# 1_8V_POWER.net
KiCad netlist of a schematic drawn in Altium Designer
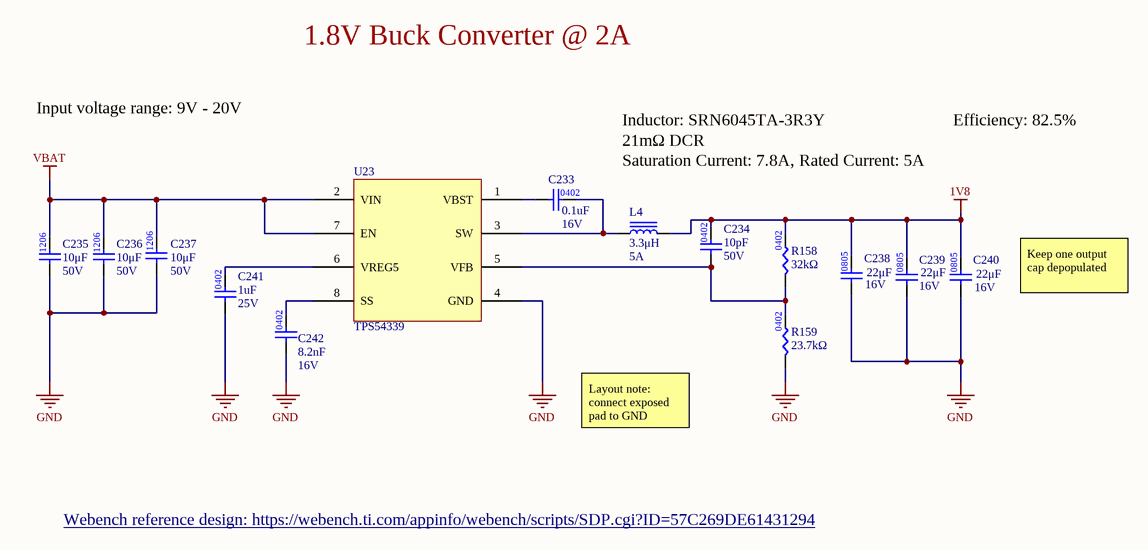
[diagram p0: 1.8V POWER.SchDoc]

(export (version "E")
  (design (tool "Eeschema 10.0.6"))
  (components
    (comp (ref "C233")
      (value "CAP_0.1uF_16V_X7R_0402")
      (footprint "CAP0402")
      (description "Ceramic Capacitor, Ceramic")
      (fields
        (field (name "MANUFACTURER") "Taiyo Yuden")
        (field (name "MANUFACTURER PART NUMBER") "LMK212AC6106MD-T")
        (field (name "RATED DC VOLTAGE (URDC)") "16V")
        (field (name "CAPACITANCE") "0.1uF")
      )
      (libsource (lib "UWRT_Schematic_Library_2020") (part "CAP_0.1uF_16V_X7R_0402"))
    )
    (comp (ref "C234")
      (value "CAP_10pF_50V_0402")
      (footprint "CAP0402")
      (fields (field (name "CAPACITANCE") "10pF") (field (name "VOLTAGE") "50V"))
      (libsource (lib "UWRT_Schematic_Library_2020") (part "CAP_10pF_50V_0402"))
    )
    (comp (ref "C235")
      (value "10μF")
      (footprint "CAP1210")
      (description "CAP CER 10UF 50V X7R 1210")
      (fields (field (name "VOLTAGE RATING") "50V") (field (name "Comment") "CAP_10uF_50V_1210"))
      (libsource (lib "UWRT_Schematic_Library_2020") (part "CAP_10uF_50V_1210"))
    )
    (comp (ref "C236")
      (value "10μF")
      (footprint "CAP1210")
      (description "CAP CER 10UF 50V X7R 1210")
      (fields (field (name "VOLTAGE RATING") "50V") (field (name "Comment") "CAP_10uF_50V_1210"))
      (libsource (lib "UWRT_Schematic_Library_2020") (part "CAP_10uF_50V_1210"))
    )
    (comp (ref "C237")
      (value "10μF")
      (footprint "CAP1210")
      (description "CAP CER 10UF 50V X7R 1210")
      (fields (field (name "VOLTAGE RATING") "50V") (field (name "Comment") "CAP_10uF_50V_1210"))
      (libsource (lib "UWRT_Schematic_Library_2020") (part "CAP_10uF_50V_1210"))
    )
    (comp (ref "C238")
      (value "22μF")
      (footprint "CAP2012")
      (description "CAP CER 22UF 16V X5R 0805")
      (fields (field (name "VOLTAGE RATING") "16V") (field (name "Comment") "CAP_22uF_16V_0805"))
      (libsource (lib "UWRT_Schematic_Library_2020") (part "CAP_22uF_16V_0805"))
    )
    (comp (ref "C239")
      (value "22μF")
      (footprint "CAP2012")
      (description "CAP CER 22UF 16V X5R 0805")
      (fields (field (name "VOLTAGE RATING") "16V") (field (name "Comment") "CAP_22uF_16V_0805"))
      (libsource (lib "UWRT_Schematic_Library_2020") (part "CAP_22uF_16V_0805"))
    )
    (comp (ref "C240")
      (value "22μF")
      (footprint "CAP2012")
      (description "CAP CER 22UF 16V X5R 0805")
      (fields (field (name "VOLTAGE RATING") "16V") (field (name "Comment") "CAP_22uF_16V_0805"))
      (libsource (lib "UWRT_Schematic_Library_2020") (part "CAP_22uF_16V_0805"))
    )
    (comp (ref "C241")
      (value "CAP_1uF_25V_0402")
      (footprint "CAP0402")
      (description "±10% 25V Ceramic Capacitor X5R 0402 (1005 Metric)")
      (fields (field (name "CAPACITANCE") "1uF") (field (name "VOLTAGE") "25V"))
      (libsource (lib "UWRT_Schematic_Library_2020") (part "CAP_1uF_25V_0402"))
    )
    (comp (ref "C242")
      (value "CAP_8.2nF_16V_0402")
      (footprint "CAP0402")
      (description "8200 pF ±10% 16V Ceramic Capacitor X7R 0402 (1005 Metric)")
      (fields (field (name "CAPACITANCE") "8.2nF") (field (name "VOLTAGE") "16V"))
      (libsource (lib "UWRT_Schematic_Library_2020") (part "CAP_8.2nF_16V_0402"))
    )
    (comp (ref "L4")
      (value "IND_3.3uH_5A")
      (footprint "IND_SRN6045TA-3R3Y")
      (description "FIXED IND 3.3UH 5A 21 MOHM SMD")
      (fields (field (name "CURRENT RATING") "5A") (field (name "INDUCTANCE") "3.3μH"))
      (libsource (lib "UWRT_Schematic_Library_2020") (part "IND_3.3uH_5A"))
    )
    (comp (ref "R158")
      (value "32kΩ")
      (footprint "RES0402")
      (description "RES 32K OHM 1% 1/16W 0402")
      (fields (field (name "TOLERANCE") "1%") (field (name "Comment") "RES_32kΩ_0402_1%"))
      (libsource (lib "UWRT_Schematic_Library_2020") (part "RES_32kΩ_0402_1%"))
    )
    (comp (ref "R159")
      (value "23.7kΩ")
      (footprint "RES0402")
      (description "RES 23.7K OHM 1% 1/16W 0402")
      (fields (field (name "POWER") "0.063W, 1/16W") (field (name "TOLERANCE") "1%"))
      (libsource (lib "UWRT_Schematic_Library_2020") (part "RES_23.7kΩ_0402_1%"))
    )
    (comp (ref "U23")
      (value "TPS54339")
      (footprint "VREG_LM5017MR/NOPB")
      (description "IC REG BUCK ADJUSTABLE 3A 8SOPWR")
      (libsource (lib "UWRT_Schematic_Library_2020") (part "TPS54339"))
    )
  )
  (nets
    (net (code "1") (name "1V8") (class "Default")
      (node (ref "C234") (pin "2") (pinfunction "2_2") (pintype "passive"))
      (node (ref "C238") (pin "2") (pinfunction "2_2") (pintype "passive"))
      (node (ref "C239") (pin "2") (pinfunction "2_2") (pintype "passive"))
      (node (ref "C240") (pin "2") (pinfunction "2_2") (pintype "passive"))
      (node (ref "L4") (pin "2") (pinfunction "2_2") (pintype "passive"))
      (node (ref "R158") (pin "2") (pinfunction "2_2") (pintype "passive"))
    )
    (net (code "2") (name "GND") (class "Default")
      (node (ref "C235") (pin "1") (pinfunction "1_1") (pintype "passive"))
      (node (ref "C236") (pin "1") (pinfunction "1_1") (pintype "passive"))
      (node (ref "C237") (pin "1") (pinfunction "1_1") (pintype "passive"))
      (node (ref "C238") (pin "1") (pinfunction "1_1") (pintype "passive"))
      (node (ref "C239") (pin "1") (pinfunction "1_1") (pintype "passive"))
      (node (ref "C240") (pin "1") (pinfunction "1_1") (pintype "passive"))
      (node (ref "C241") (pin "1") (pinfunction "1_1") (pintype "passive"))
      (node (ref "C242") (pin "1") (pinfunction "1_1") (pintype "passive"))
      (node (ref "R159") (pin "1") (pinfunction "1_1") (pintype "passive"))
      (node (ref "U23") (pin "4") (pinfunction "GND_4") (pintype "passive"))
    )
    (net (code "3") (name "Net-(U23-SS)") (class "Default")
      (node (ref "C242") (pin "2") (pinfunction "2_2") (pintype "passive"))
      (node (ref "U23") (pin "8") (pinfunction "SS_8") (pintype "passive"))
    )
    (net (code "4") (name "Net-(U23-SW)") (class "Default")
      (node (ref "C233") (pin "2") (pinfunction "2_2") (pintype "passive"))
      (node (ref "L4") (pin "1") (pinfunction "1_1") (pintype "passive"))
      (node (ref "U23") (pin "3") (pinfunction "SW_3") (pintype "passive"))
    )
    (net (code "5") (name "Net-(U23-VBST)") (class "Default")
      (node (ref "C233") (pin "1") (pinfunction "1_1") (pintype "passive"))
      (node (ref "U23") (pin "1") (pinfunction "VBST_1") (pintype "passive"))
    )
    (net (code "6") (name "Net-(U23-VFB)") (class "Default")
      (node (ref "C234") (pin "1") (pinfunction "1_1") (pintype "passive"))
      (node (ref "R158") (pin "1") (pinfunction "1_1") (pintype "passive"))
      (node (ref "R159") (pin "2") (pinfunction "2_2") (pintype "passive"))
      (node (ref "U23") (pin "5") (pinfunction "VFB_5") (pintype "passive"))
    )
    (net (code "7") (name "Net-(U23-VREG5)") (class "Default")
      (node (ref "C241") (pin "2") (pinfunction "2_2") (pintype "passive"))
      (node (ref "U23") (pin "6") (pinfunction "VREG5_6") (pintype "passive"))
    )
    (net (code "8") (name "VBAT") (class "Default")
      (node (ref "C235") (pin "2") (pinfunction "2_2") (pintype "passive"))
      (node (ref "C236") (pin "2") (pinfunction "2_2") (pintype "passive"))
      (node (ref "C237") (pin "2") (pinfunction "2_2") (pintype "passive"))
      (node (ref "U23") (pin "2") (pinfunction "VIN_2") (pintype "passive"))
      (node (ref "U23") (pin "7") (pinfunction "EN_7") (pintype "passive"))
    )
  )
)
